# emb_3y_project_2020-11-04_04-35-24.net
KiCad netlist of a schematic drawn in EasyEDA
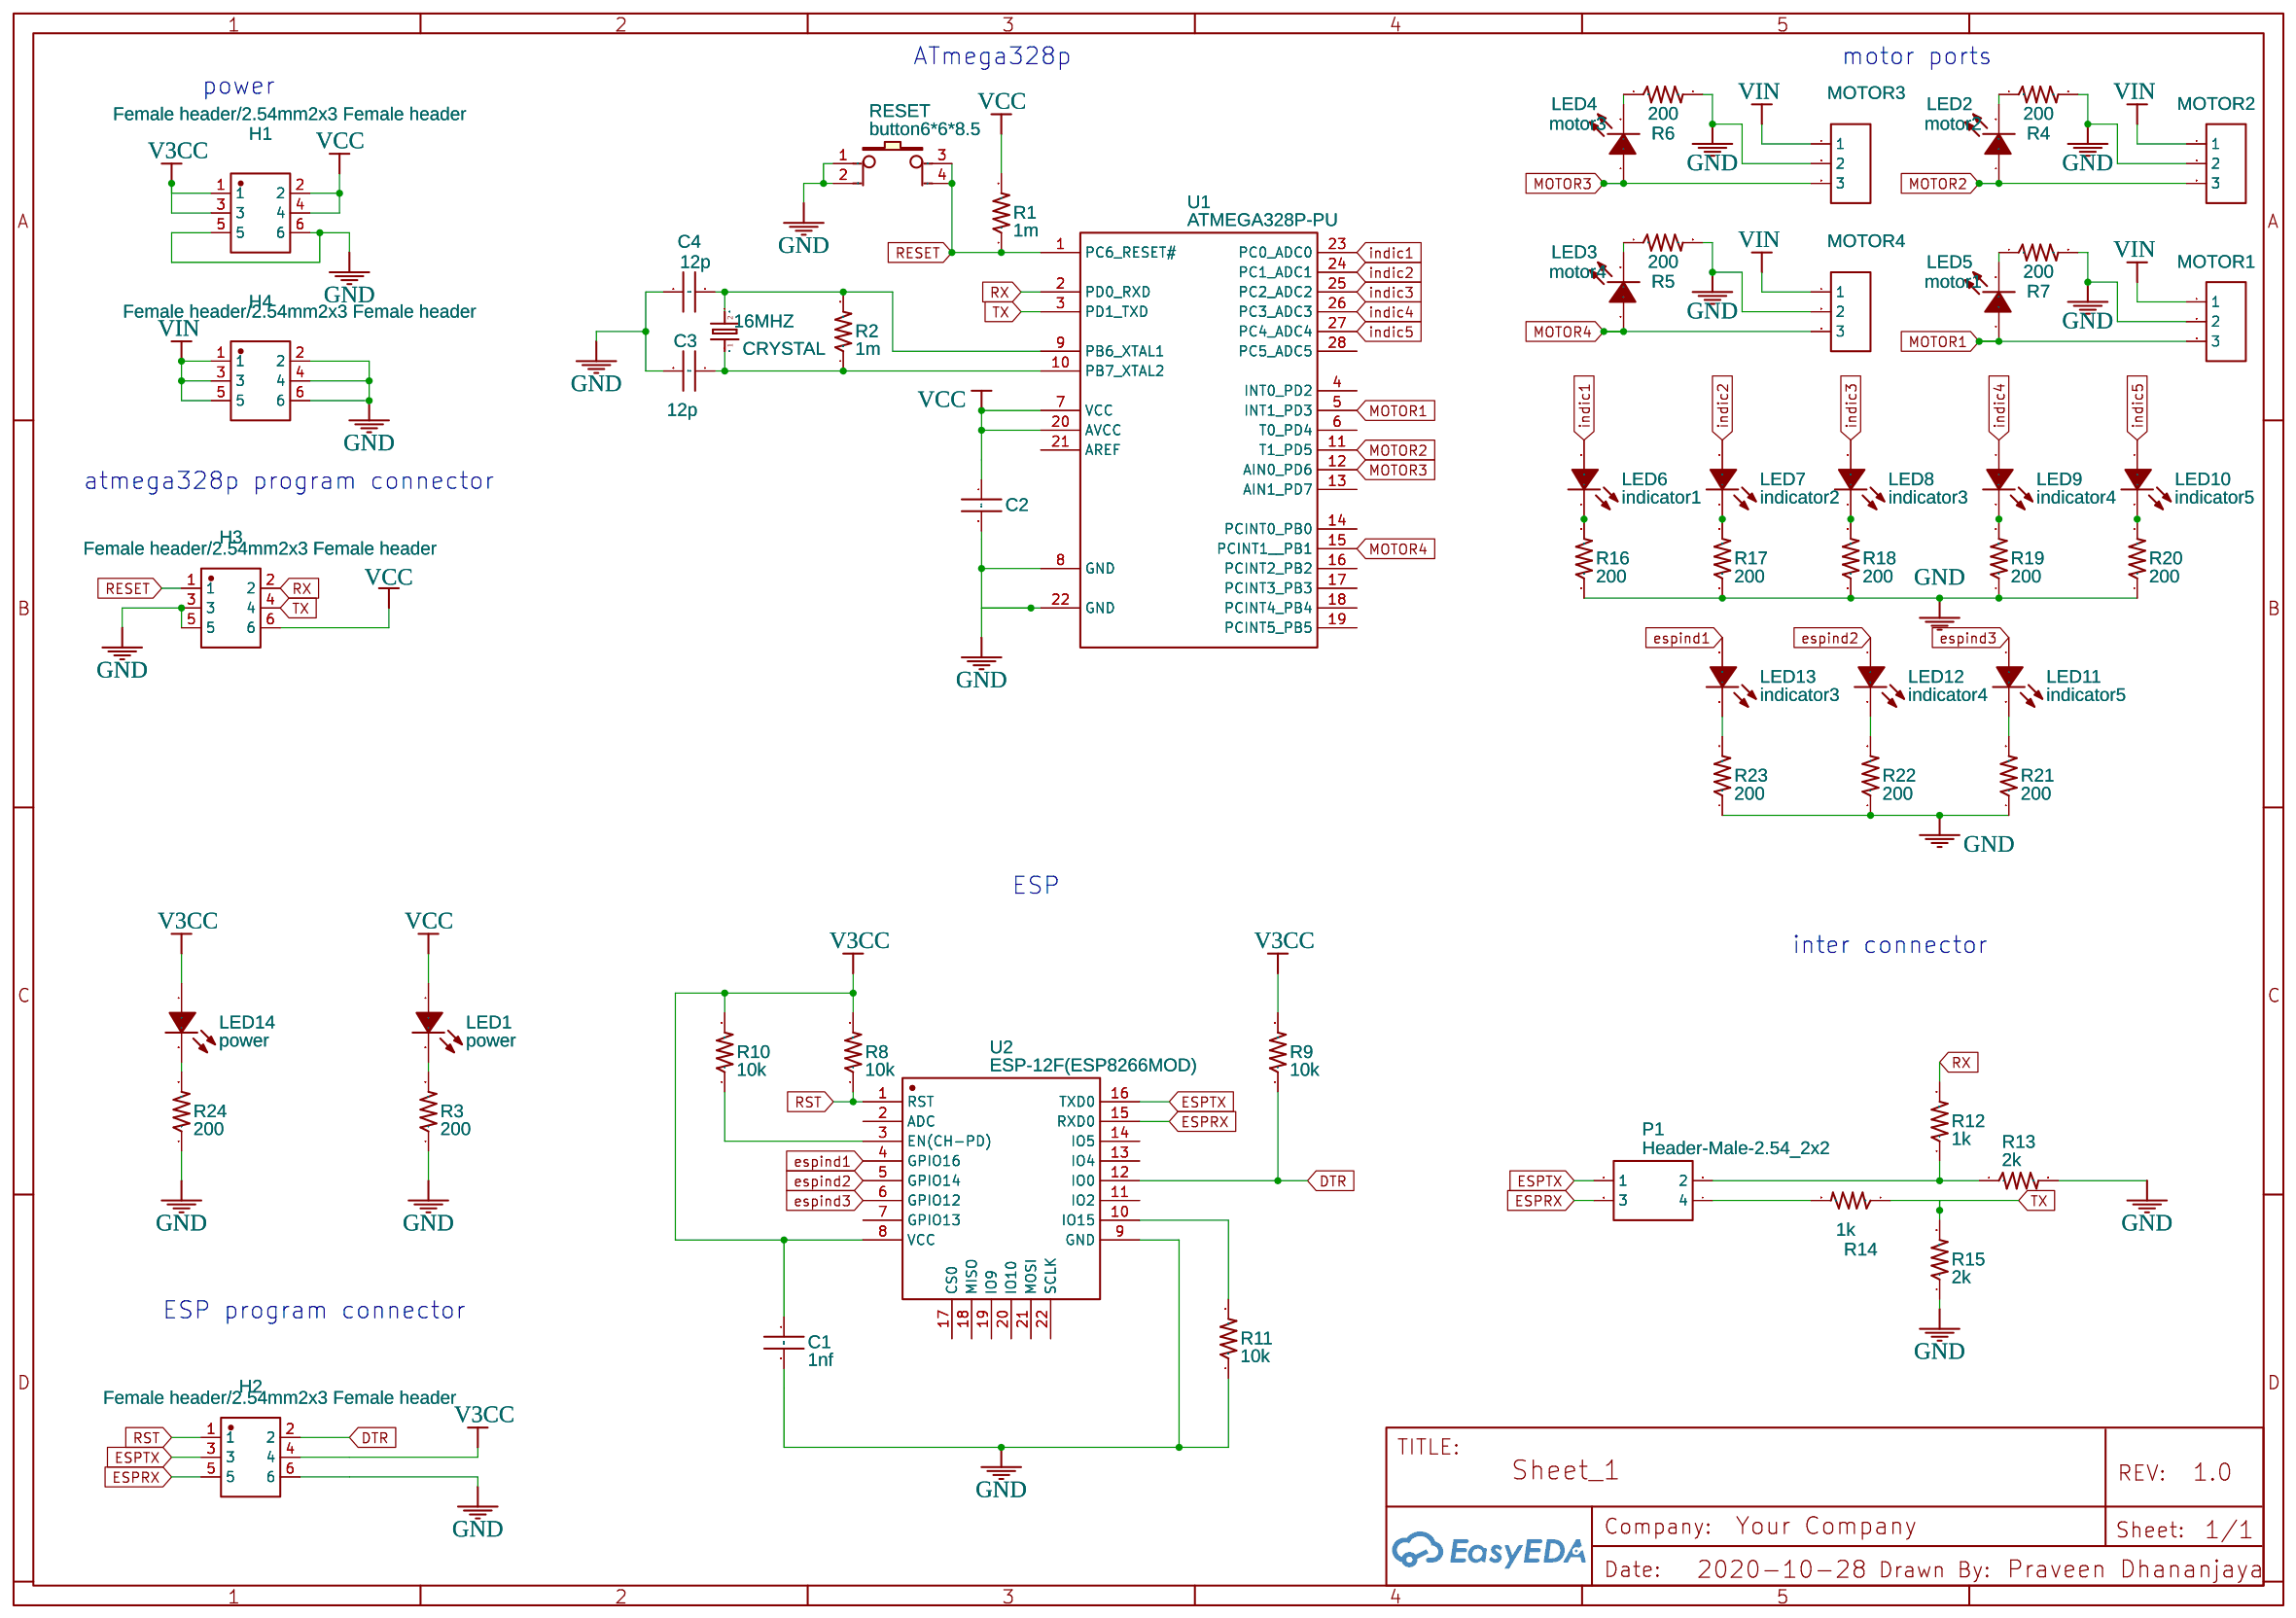
[diagram p0: schematic sheet]

(export (version "E")
  (design (tool "Eeschema 10.0.6"))
  (components
    (comp (ref "16MHZ") (value "CRYSTAL") (libsource (lib "") (part "CRYSTAL")))
    (comp (ref "C1")
      (value "1nf")
      (fields
        (field (name "BOM_Manufacturer Part") "CL21C910JBANNNC")
        (field (name "BOM_Supplier Part") "1276-1836-1-ND")
      )
      (libsource (lib "") (part "CL21C910JBANNNC_2"))
    )
    (comp (ref "C2")
      (value "12p")
      (fields
        (field (name "BOM_Manufacturer Part") "CL21C910JBANNNC")
        (field (name "BOM_Supplier Part") "1276-1836-1-ND")
      )
      (libsource (lib "") (part "CL21C910JBANNNC"))
    )
    (comp (ref "C3")
      (value "12p")
      (fields
        (field (name "BOM_Manufacturer Part") "CL21C910JBANNNC")
        (field (name "BOM_Supplier Part") "1276-1836-1-ND")
      )
      (libsource (lib "") (part "CL21C910JBANNNC_1"))
    )
    (comp (ref "C4")
      (value "12p")
      (fields
        (field (name "BOM_Manufacturer Part") "CL21C910JBANNNC")
        (field (name "BOM_Supplier Part") "1276-1836-1-ND")
      )
      (libsource (lib "") (part "CL21C910JBANNNC_1"))
    )
    (comp (ref "H1")
      (value "Female header/2.54mm2x3 Female header")
      (fields (field (name "BOM_Supplier Part") "C47552"))
      (libsource (lib "") (part "Female header/2.54mm2x3 Female header"))
    )
    (comp (ref "H2")
      (value "Female header/2.54mm2x3 Female header")
      (fields (field (name "BOM_Supplier Part") "C47552"))
      (libsource (lib "") (part "Female header/2.54mm2x3 Female header"))
    )
    (comp (ref "H3")
      (value "Female header/2.54mm2x3 Female header")
      (fields (field (name "BOM_Supplier Part") "C47552"))
      (libsource (lib "") (part "Female header/2.54mm2x3 Female header"))
    )
    (comp (ref "H4")
      (value "Female header/2.54mm2x3 Female header")
      (fields (field (name "BOM_Supplier Part") "C47552"))
      (libsource (lib "") (part "Female header/2.54mm2x3 Female header"))
    )
    (comp (ref "LED1")
      (value "power")
      (fields
        (field (name "BOM_Manufacturer Part") "LEDOrange orange 3AO4UD")
        (field (name "BOM_Supplier Part") "C62095")
      )
      (libsource (lib "") (part "LEDOrange orange 3AO4UD"))
    )
    (comp (ref "LED2")
      (value "motor2")
      (fields
        (field (name "BOM_Manufacturer Part") "LEDOrange orange 3AO4UD")
        (field (name "BOM_Supplier Part") "C62095")
      )
      (libsource (lib "") (part "LEDOrange orange 3AO4UD_1"))
    )
    (comp (ref "LED3")
      (value "motor4")
      (fields
        (field (name "BOM_Manufacturer Part") "LEDOrange orange 3AO4UD")
        (field (name "BOM_Supplier Part") "C62095")
      )
      (libsource (lib "") (part "LEDOrange orange 3AO4UD_1"))
    )
    (comp (ref "LED4")
      (value "motor3")
      (fields
        (field (name "BOM_Manufacturer Part") "LEDOrange orange 3AO4UD")
        (field (name "BOM_Supplier Part") "C62095")
      )
      (libsource (lib "") (part "LEDOrange orange 3AO4UD_1"))
    )
    (comp (ref "LED5")
      (value "motor1")
      (fields
        (field (name "BOM_Manufacturer Part") "LEDOrange orange 3AO4UD")
        (field (name "BOM_Supplier Part") "C62095")
      )
      (libsource (lib "") (part "LEDOrange orange 3AO4UD_1"))
    )
    (comp (ref "LED6")
      (value "indicator1")
      (fields
        (field (name "BOM_Manufacturer Part") "LEDOrange orange 3AO4UD")
        (field (name "BOM_Supplier Part") "C62095")
      )
      (libsource (lib "") (part "LEDOrange orange 3AO4UD"))
    )
    (comp (ref "LED7")
      (value "indicator2")
      (fields
        (field (name "BOM_Manufacturer Part") "LEDOrange orange 3AO4UD")
        (field (name "BOM_Supplier Part") "C62095")
      )
      (libsource (lib "") (part "LEDOrange orange 3AO4UD"))
    )
    (comp (ref "LED8")
      (value "indicator3")
      (fields
        (field (name "BOM_Manufacturer Part") "LEDOrange orange 3AO4UD")
        (field (name "BOM_Supplier Part") "C62095")
      )
      (libsource (lib "") (part "LEDOrange orange 3AO4UD"))
    )
    (comp (ref "LED9")
      (value "indicator4")
      (fields
        (field (name "BOM_Manufacturer Part") "LEDOrange orange 3AO4UD")
        (field (name "BOM_Supplier Part") "C62095")
      )
      (libsource (lib "") (part "LEDOrange orange 3AO4UD"))
    )
    (comp (ref "LED10")
      (value "indicator5")
      (fields
        (field (name "BOM_Manufacturer Part") "LEDOrange orange 3AO4UD")
        (field (name "BOM_Supplier Part") "C62095")
      )
      (libsource (lib "") (part "LEDOrange orange 3AO4UD"))
    )
    (comp (ref "LED11")
      (value "indicator5")
      (fields
        (field (name "BOM_Manufacturer Part") "LEDOrange orange 3AO4UD")
        (field (name "BOM_Supplier Part") "C62095")
      )
      (libsource (lib "") (part "LEDOrange orange 3AO4UD"))
    )
    (comp (ref "LED12")
      (value "indicator4")
      (fields
        (field (name "BOM_Manufacturer Part") "LEDOrange orange 3AO4UD")
        (field (name "BOM_Supplier Part") "C62095")
      )
      (libsource (lib "") (part "LEDOrange orange 3AO4UD"))
    )
    (comp (ref "LED13")
      (value "indicator3")
      (fields
        (field (name "BOM_Manufacturer Part") "LEDOrange orange 3AO4UD")
        (field (name "BOM_Supplier Part") "C62095")
      )
      (libsource (lib "") (part "LEDOrange orange 3AO4UD"))
    )
    (comp (ref "LED14")
      (value "power")
      (fields
        (field (name "BOM_Manufacturer Part") "LEDOrange orange 3AO4UD")
        (field (name "BOM_Supplier Part") "C62095")
      )
      (libsource (lib "") (part "LEDOrange orange 3AO4UD"))
    )
    (comp (ref "MOTOR1")
      (value "Header-Male-2.54_1x3")
      (fields
        (field (name "BOM_Manufacturer Part") "Header2.54mm 1*3P")
        (field (name "BOM_Supplier Part") "C49257")
      )
      (libsource (lib "") (part "Header-Male-2.54_1x3"))
    )
    (comp (ref "MOTOR2")
      (value "Header-Male-2.54_1x3")
      (fields
        (field (name "BOM_Manufacturer Part") "Header2.54mm 1*3P")
        (field (name "BOM_Supplier Part") "C49257")
      )
      (libsource (lib "") (part "Header-Male-2.54_1x3"))
    )
    (comp (ref "MOTOR3")
      (value "Header-Male-2.54_1x3")
      (fields
        (field (name "BOM_Manufacturer Part") "Header2.54mm 1*3P")
        (field (name "BOM_Supplier Part") "C49257")
      )
      (libsource (lib "") (part "Header-Male-2.54_1x3"))
    )
    (comp (ref "MOTOR4")
      (value "Header-Male-2.54_1x3")
      (fields
        (field (name "BOM_Manufacturer Part") "Header2.54mm 1*3P")
        (field (name "BOM_Supplier Part") "C49257")
      )
      (libsource (lib "") (part "Header-Male-2.54_1x3"))
    )
    (comp (ref "P1")
      (value "Header-Male-2.54_2x2")
      (fields
        (field (name "BOM_Manufacturer Part") "Double Rows2.54mm2*2pHeaders  Pins")
        (field (name "BOM_Supplier Part") "C66690")
      )
      (libsource (lib "") (part "Header-Male-2.54_2x2"))
    )
    (comp (ref "R1")
      (value "1m")
      (fields (field (name "BOM_Manufacturer Part") "SAMTECH"))
      (libsource (lib "") (part "R_US805"))
    )
    (comp (ref "R2")
      (value "1m")
      (fields (field (name "BOM_Manufacturer Part") "SAMTECH"))
      (libsource (lib "") (part "R_US805"))
    )
    (comp (ref "R3")
      (value "200")
      (fields (field (name "BOM_Manufacturer Part") "SAMTECH"))
      (libsource (lib "") (part "R_US805"))
    )
    (comp (ref "R4")
      (value "200")
      (fields (field (name "BOM_Manufacturer Part") "SAMTECH"))
      (libsource (lib "") (part "R_US805_2"))
    )
    (comp (ref "R5")
      (value "200")
      (fields (field (name "BOM_Manufacturer Part") "SAMTECH"))
      (libsource (lib "") (part "R_US805_2"))
    )
    (comp (ref "R6")
      (value "200")
      (fields (field (name "BOM_Manufacturer Part") "SAMTECH"))
      (libsource (lib "") (part "R_US805_2"))
    )
    (comp (ref "R7")
      (value "200")
      (fields (field (name "BOM_Manufacturer Part") "SAMTECH"))
      (libsource (lib "") (part "R_US805_2"))
    )
    (comp (ref "R8")
      (value "10k")
      (fields (field (name "BOM_Manufacturer Part") "SAMTECH"))
      (libsource (lib "") (part "R_US805"))
    )
    (comp (ref "R9")
      (value "10k")
      (fields (field (name "BOM_Manufacturer Part") "SAMTECH"))
      (libsource (lib "") (part "R_US805"))
    )
    (comp (ref "R10")
      (value "10k")
      (fields (field (name "BOM_Manufacturer Part") "SAMTECH"))
      (libsource (lib "") (part "R_US805"))
    )
    (comp (ref "R11")
      (value "10k")
      (fields (field (name "BOM_Manufacturer Part") "SAMTECH"))
      (libsource (lib "") (part "R_US805"))
    )
    (comp (ref "R12")
      (value "1k")
      (fields (field (name "BOM_Manufacturer Part") "SAMTECH"))
      (libsource (lib "") (part "R_US805"))
    )
    (comp (ref "R13")
      (value "2k")
      (fields (field (name "BOM_Manufacturer Part") "SAMTECH"))
      (libsource (lib "") (part "R_US805_2"))
    )
    (comp (ref "R14")
      (value "1k")
      (fields (field (name "BOM_Manufacturer Part") "SAMTECH"))
      (libsource (lib "") (part "R_US805_1"))
    )
    (comp (ref "R15")
      (value "2k")
      (fields (field (name "BOM_Manufacturer Part") "SAMTECH"))
      (libsource (lib "") (part "R_US805"))
    )
    (comp (ref "R16")
      (value "200")
      (fields (field (name "BOM_Manufacturer Part") "SAMTECH"))
      (libsource (lib "") (part "R_US805"))
    )
    (comp (ref "R17")
      (value "200")
      (fields (field (name "BOM_Manufacturer Part") "SAMTECH"))
      (libsource (lib "") (part "R_US805"))
    )
    (comp (ref "R18")
      (value "200")
      (fields (field (name "BOM_Manufacturer Part") "SAMTECH"))
      (libsource (lib "") (part "R_US805"))
    )
    (comp (ref "R19")
      (value "200")
      (fields (field (name "BOM_Manufacturer Part") "SAMTECH"))
      (libsource (lib "") (part "R_US805"))
    )
    (comp (ref "R20")
      (value "200")
      (fields (field (name "BOM_Manufacturer Part") "SAMTECH"))
      (libsource (lib "") (part "R_US805"))
    )
    (comp (ref "R21")
      (value "200")
      (fields (field (name "BOM_Manufacturer Part") "SAMTECH"))
      (libsource (lib "") (part "R_US805"))
    )
    (comp (ref "R22")
      (value "200")
      (fields (field (name "BOM_Manufacturer Part") "SAMTECH"))
      (libsource (lib "") (part "R_US805"))
    )
    (comp (ref "R23")
      (value "200")
      (fields (field (name "BOM_Manufacturer Part") "SAMTECH"))
      (libsource (lib "") (part "R_US805"))
    )
    (comp (ref "R24")
      (value "200")
      (fields (field (name "BOM_Manufacturer Part") "SAMTECH"))
      (libsource (lib "") (part "R_US805"))
    )
    (comp (ref "RESET")
      (value "button6*6*8.5")
      (fields (field (name "BOM_Supplier Part") "C59980"))
      (libsource (lib "") (part "button6*6*8.5"))
    )
    (comp (ref "U1")
      (value "ATMEGA328P-PU")
      (fields (field (name "BOM_Supplier Part") "C33901"))
      (libsource (lib "") (part "ATMEGA328P-PU"))
    )
    (comp (ref "U2")
      (value "ESP-12F(ESP8266MOD)")
      (fields (field (name "BOM_Supplier Part") "C82891"))
      (libsource (lib "") (part "ESP-12F(ESP8266MOD)"))
    )
  )
  (nets
    (net (code "1") (name "DTR") (class "Default")
      (node (ref "H2") (pin "2") (pinfunction "2_2") (pintype "unspecified"))
      (node (ref "R9") (pin "1") (pinfunction "1_1") (pintype "unspecified"))
      (node (ref "U2") (pin "12") (pinfunction "IO0_12") (pintype "unspecified"))
    )
    (net (code "2") (name "ESPRX") (class "Default")
      (node (ref "H2") (pin "5") (pinfunction "5_5") (pintype "unspecified"))
      (node (ref "P1") (pin "3") (pinfunction "3_3") (pintype "input"))
      (node (ref "U2") (pin "15") (pinfunction "RXD0_15") (pintype "unspecified"))
    )
    (net (code "3") (name "ESPTX") (class "Default")
      (node (ref "H2") (pin "3") (pinfunction "3_3") (pintype "unspecified"))
      (node (ref "P1") (pin "1") (pinfunction "1_1") (pintype "input"))
      (node (ref "U2") (pin "16") (pinfunction "TXD0_16") (pintype "unspecified"))
    )
    (net (code "4") (name "GND") (class "Default")
      (node (ref "C1") (pin "1") (pinfunction "1_1") (pintype "unspecified"))
      (node (ref "C2") (pin "2") (pinfunction "2_2") (pintype "unspecified"))
      (node (ref "C3") (pin "2") (pinfunction "2_2") (pintype "unspecified"))
      (node (ref "C4") (pin "2") (pinfunction "2_2") (pintype "unspecified"))
      (node (ref "H1") (pin "5") (pinfunction "5_5") (pintype "unspecified"))
      (node (ref "H1") (pin "6") (pinfunction "6_6") (pintype "unspecified"))
      (node (ref "H2") (pin "6") (pinfunction "6_6") (pintype "unspecified"))
      (node (ref "H3") (pin "3") (pinfunction "3_3") (pintype "unspecified"))
      (node (ref "H3") (pin "5") (pinfunction "5_5") (pintype "unspecified"))
      (node (ref "H4") (pin "2") (pinfunction "2_2") (pintype "unspecified"))
      (node (ref "H4") (pin "4") (pinfunction "4_4") (pintype "unspecified"))
      (node (ref "H4") (pin "6") (pinfunction "6_6") (pintype "unspecified"))
      (node (ref "MOTOR1") (pin "2") (pinfunction "2_2") (pintype "input"))
      (node (ref "MOTOR2") (pin "2") (pinfunction "2_2") (pintype "input"))
      (node (ref "MOTOR3") (pin "2") (pinfunction "2_2") (pintype "input"))
      (node (ref "MOTOR4") (pin "2") (pinfunction "2_2") (pintype "input"))
      (node (ref "R11") (pin "1") (pinfunction "1_1") (pintype "unspecified"))
      (node (ref "R13") (pin "2") (pinfunction "2_2") (pintype "unspecified"))
      (node (ref "R15") (pin "1") (pinfunction "1_1") (pintype "unspecified"))
      (node (ref "R16") (pin "1") (pinfunction "1_1") (pintype "unspecified"))
      (node (ref "R17") (pin "1") (pinfunction "1_1") (pintype "unspecified"))
      (node (ref "R18") (pin "1") (pinfunction "1_1") (pintype "unspecified"))
      (node (ref "R19") (pin "1") (pinfunction "1_1") (pintype "unspecified"))
      (node (ref "R20") (pin "1") (pinfunction "1_1") (pintype "unspecified"))
      (node (ref "R21") (pin "1") (pinfunction "1_1") (pintype "unspecified"))
      (node (ref "R22") (pin "1") (pinfunction "1_1") (pintype "unspecified"))
      (node (ref "R23") (pin "1") (pinfunction "1_1") (pintype "unspecified"))
      (node (ref "R24") (pin "1") (pinfunction "1_1") (pintype "unspecified"))
      (node (ref "R3") (pin "1") (pinfunction "1_1") (pintype "unspecified"))
      (node (ref "R4") (pin "2") (pinfunction "2_2") (pintype "unspecified"))
      (node (ref "R5") (pin "2") (pinfunction "2_2") (pintype "unspecified"))
      (node (ref "R6") (pin "2") (pinfunction "2_2") (pintype "unspecified"))
      (node (ref "R7") (pin "2") (pinfunction "2_2") (pintype "unspecified"))
      (node (ref "RESET") (pin "1") (pinfunction "1_1") (pintype "input"))
      (node (ref "RESET") (pin "2") (pinfunction "2_2") (pintype "input"))
      (node (ref "U1") (pin "22") (pinfunction "GND_22") (pintype "passive"))
      (node (ref "U1") (pin "8") (pinfunction "GND_8") (pintype "passive"))
      (node (ref "U2") (pin "9") (pinfunction "GND_9") (pintype "unspecified"))
    )
    (net (code "5") (name "MOTOR1") (class "Default")
      (node (ref "LED5") (pin "1") (pinfunction "A_1") (pintype "unspecified"))
      (node (ref "MOTOR1") (pin "3") (pinfunction "3_3") (pintype "input"))
      (node (ref "U1") (pin "5") (pinfunction "INT1_PD3_5") (pintype "bidirectional"))
    )
    (net (code "6") (name "MOTOR2") (class "Default")
      (node (ref "LED2") (pin "1") (pinfunction "A_1") (pintype "unspecified"))
      (node (ref "MOTOR2") (pin "3") (pinfunction "3_3") (pintype "input"))
      (node (ref "U1") (pin "11") (pinfunction "T1_PD5_11") (pintype "bidirectional"))
    )
    (net (code "7") (name "MOTOR3") (class "Default")
      (node (ref "LED4") (pin "1") (pinfunction "A_1") (pintype "unspecified"))
      (node (ref "MOTOR3") (pin "3") (pinfunction "3_3") (pintype "input"))
      (node (ref "U1") (pin "12") (pinfunction "AIN0_PD6_12") (pintype "bidirectional"))
    )
    (net (code "8") (name "MOTOR4") (class "Default")
      (node (ref "LED3") (pin "1") (pinfunction "A_1") (pintype "unspecified"))
      (node (ref "MOTOR4") (pin "3") (pinfunction "3_3") (pintype "input"))
      (node (ref "U1") (pin "15") (pinfunction "PCINT1__PB1_15") (pintype "bidirectional"))
    )
    (net (code "9") (name "Net-(LED1-K)") (class "Default")
      (node (ref "LED1") (pin "2") (pinfunction "K_2") (pintype "unspecified"))
      (node (ref "R3") (pin "2") (pinfunction "2_2") (pintype "unspecified"))
    )
    (net (code "10") (name "Net-(LED2-K)") (class "Default")
      (node (ref "LED2") (pin "2") (pinfunction "K_2") (pintype "unspecified"))
      (node (ref "R4") (pin "1") (pinfunction "1_1") (pintype "unspecified"))
    )
    (net (code "11") (name "Net-(LED3-K)") (class "Default")
      (node (ref "LED3") (pin "2") (pinfunction "K_2") (pintype "unspecified"))
      (node (ref "R5") (pin "1") (pinfunction "1_1") (pintype "unspecified"))
    )
    (net (code "12") (name "Net-(LED4-K)") (class "Default")
      (node (ref "LED4") (pin "2") (pinfunction "K_2") (pintype "unspecified"))
      (node (ref "R6") (pin "1") (pinfunction "1_1") (pintype "unspecified"))
    )
    (net (code "13") (name "Net-(LED5-K)") (class "Default")
      (node (ref "LED5") (pin "2") (pinfunction "K_2") (pintype "unspecified"))
      (node (ref "R7") (pin "1") (pinfunction "1_1") (pintype "unspecified"))
    )
    (net (code "14") (name "Net-(LED6-K)") (class "Default")
      (node (ref "LED6") (pin "2") (pinfunction "K_2") (pintype "unspecified"))
      (node (ref "R16") (pin "2") (pinfunction "2_2") (pintype "unspecified"))
    )
    (net (code "15") (name "Net-(LED7-K)") (class "Default")
      (node (ref "LED7") (pin "2") (pinfunction "K_2") (pintype "unspecified"))
      (node (ref "R17") (pin "2") (pinfunction "2_2") (pintype "unspecified"))
    )
    (net (code "16") (name "Net-(LED8-K)") (class "Default")
      (node (ref "LED8") (pin "2") (pinfunction "K_2") (pintype "unspecified"))
      (node (ref "R18") (pin "2") (pinfunction "2_2") (pintype "unspecified"))
    )
    (net (code "17") (name "Net-(LED9-K)") (class "Default")
      (node (ref "LED9") (pin "2") (pinfunction "K_2") (pintype "unspecified"))
      (node (ref "R19") (pin "2") (pinfunction "2_2") (pintype "unspecified"))
    )
    (net (code "18") (name "Net-(LED10-K)") (class "Default")
      (node (ref "LED10") (pin "2") (pinfunction "K_2") (pintype "unspecified"))
      (node (ref "R20") (pin "2") (pinfunction "2_2") (pintype "unspecified"))
    )
    (net (code "19") (name "Net-(LED11-K)") (class "Default")
      (node (ref "LED11") (pin "2") (pinfunction "K_2") (pintype "unspecified"))
      (node (ref "R21") (pin "2") (pinfunction "2_2") (pintype "unspecified"))
    )
    (net (code "20") (name "Net-(LED12-K)") (class "Default")
      (node (ref "LED12") (pin "2") (pinfunction "K_2") (pintype "unspecified"))
      (node (ref "R22") (pin "2") (pinfunction "2_2") (pintype "unspecified"))
    )
    (net (code "21") (name "Net-(LED13-K)") (class "Default")
      (node (ref "LED13") (pin "2") (pinfunction "K_2") (pintype "unspecified"))
      (node (ref "R23") (pin "2") (pinfunction "2_2") (pintype "unspecified"))
    )
    (net (code "22") (name "Net-(LED14-K)") (class "Default")
      (node (ref "LED14") (pin "2") (pinfunction "K_2") (pintype "unspecified"))
      (node (ref "R24") (pin "2") (pinfunction "2_2") (pintype "unspecified"))
    )
    (net (code "23") (name "Net-(P1-Pad2)") (class "Default")
      (node (ref "P1") (pin "2") (pinfunction "2_2") (pintype "input"))
      (node (ref "R12") (pin "1") (pinfunction "1_1") (pintype "unspecified"))
      (node (ref "R13") (pin "1") (pinfunction "1_1") (pintype "unspecified"))
    )
    (net (code "24") (name "Net-(P1-Pad4)") (class "Default")
      (node (ref "P1") (pin "4") (pinfunction "4_4") (pintype "input"))
      (node (ref "R14") (pin "2") (pinfunction "2_2") (pintype "unspecified"))
    )
    (net (code "25") (name "Net-(U1-PB6_XTAL1)") (class "Default")
      (node (ref "16MHZ") (pin "2") (pinfunction "2_2") (pintype "unspecified"))
      (node (ref "C4") (pin "1") (pinfunction "1_1") (pintype "unspecified"))
      (node (ref "R2") (pin "2") (pinfunction "2_2") (pintype "unspecified"))
      (node (ref "U1") (pin "9") (pinfunction "PB6_XTAL1_9") (pintype "bidirectional"))
    )
    (net (code "26") (name "Net-(U1-PB7_XTAL2)") (class "Default")
      (node (ref "16MHZ") (pin "1") (pinfunction "1_1") (pintype "unspecified"))
      (node (ref "C3") (pin "1") (pinfunction "1_1") (pintype "unspecified"))
      (node (ref "R2") (pin "1") (pinfunction "1_1") (pintype "unspecified"))
      (node (ref "U1") (pin "10") (pinfunction "PB7_XTAL2_10") (pintype "bidirectional"))
    )
    (net (code "27") (name "Net-(U2-EN(CH-PD))") (class "Default")
      (node (ref "R10") (pin "1") (pinfunction "1_1") (pintype "unspecified"))
      (node (ref "U2") (pin "3") (pinfunction "EN(CH-PD)_3") (pintype "unspecified"))
    )
    (net (code "28") (name "Net-(U2-IO15)") (class "Default")
      (node (ref "R11") (pin "2") (pinfunction "2_2") (pintype "unspecified"))
      (node (ref "U2") (pin "10") (pinfunction "IO15_10") (pintype "unspecified"))
    )
    (net (code "29") (name "RESET") (class "Default")
      (node (ref "H3") (pin "1") (pinfunction "1_1") (pintype "unspecified"))
      (node (ref "R1") (pin "1") (pinfunction "1_1") (pintype "unspecified"))
      (node (ref "RESET") (pin "3") (pinfunction "3_3") (pintype "input"))
      (node (ref "RESET") (pin "4") (pinfunction "4_4") (pintype "input"))
      (node (ref "U1") (pin "1") (pinfunction "PC6_RESET#_1") (pintype "bidirectional"))
    )
    (net (code "30") (name "RST") (class "Default")
      (node (ref "H2") (pin "1") (pinfunction "1_1") (pintype "unspecified"))
      (node (ref "R8") (pin "1") (pinfunction "1_1") (pintype "unspecified"))
      (node (ref "U2") (pin "1") (pinfunction "RST_1") (pintype "unspecified"))
    )
    (net (code "31") (name "RX") (class "Default")
      (node (ref "H3") (pin "2") (pinfunction "2_2") (pintype "unspecified"))
      (node (ref "R12") (pin "2") (pinfunction "2_2") (pintype "unspecified"))
      (node (ref "U1") (pin "2") (pinfunction "PD0_RXD_2") (pintype "bidirectional"))
    )
    (net (code "32") (name "TX") (class "Default")
      (node (ref "H3") (pin "4") (pinfunction "4_4") (pintype "unspecified"))
      (node (ref "R14") (pin "1") (pinfunction "1_1") (pintype "unspecified"))
      (node (ref "R15") (pin "2") (pinfunction "2_2") (pintype "unspecified"))
      (node (ref "U1") (pin "3") (pinfunction "PD1_TXD_3") (pintype "bidirectional"))
    )
    (net (code "33") (name "V3CC") (class "Default")
      (node (ref "C1") (pin "2") (pinfunction "2_2") (pintype "unspecified"))
      (node (ref "H1") (pin "1") (pinfunction "1_1") (pintype "unspecified"))
      (node (ref "H1") (pin "3") (pinfunction "3_3") (pintype "unspecified"))
      (node (ref "H2") (pin "4") (pinfunction "4_4") (pintype "unspecified"))
      (node (ref "LED14") (pin "1") (pinfunction "A_1") (pintype "unspecified"))
      (node (ref "R10") (pin "2") (pinfunction "2_2") (pintype "unspecified"))
      (node (ref "R8") (pin "2") (pinfunction "2_2") (pintype "unspecified"))
      (node (ref "R9") (pin "2") (pinfunction "2_2") (pintype "unspecified"))
      (node (ref "U2") (pin "8") (pinfunction "VCC_8") (pintype "unspecified"))
    )
    (net (code "34") (name "VCC") (class "Default")
      (node (ref "C2") (pin "1") (pinfunction "1_1") (pintype "unspecified"))
      (node (ref "H1") (pin "2") (pinfunction "2_2") (pintype "unspecified"))
      (node (ref "H1") (pin "4") (pinfunction "4_4") (pintype "unspecified"))
      (node (ref "H3") (pin "6") (pinfunction "6_6") (pintype "unspecified"))
      (node (ref "LED1") (pin "1") (pinfunction "A_1") (pintype "unspecified"))
      (node (ref "R1") (pin "2") (pinfunction "2_2") (pintype "unspecified"))
      (node (ref "U1") (pin "20") (pinfunction "AVCC_20") (pintype "passive"))
      (node (ref "U1") (pin "7") (pinfunction "VCC_7") (pintype "passive"))
    )
    (net (code "35") (name "VIN") (class "Default")
      (node (ref "H4") (pin "1") (pinfunction "1_1") (pintype "unspecified"))
      (node (ref "H4") (pin "3") (pinfunction "3_3") (pintype "unspecified"))
      (node (ref "H4") (pin "5") (pinfunction "5_5") (pintype "unspecified"))
      (node (ref "MOTOR1") (pin "1") (pinfunction "1_1") (pintype "input"))
      (node (ref "MOTOR2") (pin "1") (pinfunction "1_1") (pintype "input"))
      (node (ref "MOTOR3") (pin "1") (pinfunction "1_1") (pintype "input"))
      (node (ref "MOTOR4") (pin "1") (pinfunction "1_1") (pintype "input"))
    )
    (net (code "36") (name "espind1") (class "Default")
      (node (ref "LED13") (pin "1") (pinfunction "A_1") (pintype "unspecified"))
      (node (ref "U2") (pin "4") (pinfunction "GPIO16_4") (pintype "unspecified"))
    )
    (net (code "37") (name "espind2") (class "Default")
      (node (ref "LED12") (pin "1") (pinfunction "A_1") (pintype "unspecified"))
      (node (ref "U2") (pin "5") (pinfunction "GPIO14_5") (pintype "unspecified"))
    )
    (net (code "38") (name "espind3") (class "Default")
      (node (ref "LED11") (pin "1") (pinfunction "A_1") (pintype "unspecified"))
      (node (ref "U2") (pin "6") (pinfunction "GPIO12_6") (pintype "unspecified"))
    )
    (net (code "39") (name "indic1") (class "Default")
      (node (ref "LED6") (pin "1") (pinfunction "A_1") (pintype "unspecified"))
      (node (ref "U1") (pin "23") (pinfunction "PC0_ADC0_23") (pintype "bidirectional"))
    )
    (net (code "40") (name "indic2") (class "Default")
      (node (ref "LED7") (pin "1") (pinfunction "A_1") (pintype "unspecified"))
      (node (ref "U1") (pin "24") (pinfunction "PC1_ADC1_24") (pintype "bidirectional"))
    )
    (net (code "41") (name "indic3") (class "Default")
      (node (ref "LED8") (pin "1") (pinfunction "A_1") (pintype "unspecified"))
      (node (ref "U1") (pin "25") (pinfunction "PC2_ADC2_25") (pintype "bidirectional"))
    )
    (net (code "42") (name "indic4") (class "Default")
      (node (ref "LED9") (pin "1") (pinfunction "A_1") (pintype "unspecified"))
      (node (ref "U1") (pin "26") (pinfunction "PC3_ADC3_26") (pintype "bidirectional"))
    )
    (net (code "43") (name "indic5") (class "Default")
      (node (ref "LED10") (pin "1") (pinfunction "A_1") (pintype "unspecified"))
      (node (ref "U1") (pin "27") (pinfunction "PC4_ADC4_27") (pintype "bidirectional"))
    )
    (net (code "44") (name "unconnected-(U1-AIN1_PD7-Pad13)") (class "Default")
      (node (ref "U1") (pin "13") (pinfunction "AIN1_PD7_13") (pintype "bidirectional"))
    )
    (net (code "45") (name "unconnected-(U1-AREF-Pad21)") (class "Default")
      (node (ref "U1") (pin "21") (pinfunction "AREF_21") (pintype "passive"))
    )
    (net (code "46") (name "unconnected-(U1-INT0_PD2-Pad4)") (class "Default")
      (node (ref "U1") (pin "4") (pinfunction "INT0_PD2_4") (pintype "bidirectional"))
    )
    (net (code "47") (name "unconnected-(U1-PC5_ADC5-Pad28)") (class "Default")
      (node (ref "U1") (pin "28") (pinfunction "PC5_ADC5_28") (pintype "bidirectional"))
    )
    (net (code "48") (name "unconnected-(U1-PCINT0_PB0-Pad14)") (class "Default")
      (node (ref "U1") (pin "14") (pinfunction "PCINT0_PB0_14") (pintype "bidirectional"))
    )
    (net (code "49") (name "unconnected-(U1-PCINT2_PB2-Pad16)") (class "Default")
      (node (ref "U1") (pin "16") (pinfunction "PCINT2_PB2_16") (pintype "bidirectional"))
    )
    (net (code "50") (name "unconnected-(U1-PCINT3_PB3-Pad17)") (class "Default")
      (node (ref "U1") (pin "17") (pinfunction "PCINT3_PB3_17") (pintype "bidirectional"))
    )
    (net (code "51") (name "unconnected-(U1-PCINT4_PB4-Pad18)") (class "Default")
      (node (ref "U1") (pin "18") (pinfunction "PCINT4_PB4_18") (pintype "bidirectional"))
    )
    (net (code "52") (name "unconnected-(U1-PCINT5_PB5-Pad19)") (class "Default")
      (node (ref "U1") (pin "19") (pinfunction "PCINT5_PB5_19") (pintype "bidirectional"))
    )
    (net (code "53") (name "unconnected-(U1-T0_PD4-Pad6)") (class "Default")
      (node (ref "U1") (pin "6") (pinfunction "T0_PD4_6") (pintype "bidirectional"))
    )
    (net (code "54") (name "unconnected-(U2-ADC-Pad2)") (class "Default")
      (node (ref "U2") (pin "2") (pinfunction "ADC_2") (pintype "unspecified"))
    )
    (net (code "55") (name "unconnected-(U2-CS0-Pad17)") (class "Default")
      (node (ref "U2") (pin "17") (pinfunction "CS0_17") (pintype "unspecified"))
    )
    (net (code "56") (name "unconnected-(U2-GPIO13-Pad7)") (class "Default")
      (node (ref "U2") (pin "7") (pinfunction "GPIO13_7") (pintype "unspecified"))
    )
    (net (code "57") (name "unconnected-(U2-IO2-Pad11)") (class "Default")
      (node (ref "U2") (pin "11") (pinfunction "IO2_11") (pintype "unspecified"))
    )
    (net (code "58") (name "unconnected-(U2-IO4-Pad13)") (class "Default")
      (node (ref "U2") (pin "13") (pinfunction "IO4_13") (pintype "unspecified"))
    )
    (net (code "59") (name "unconnected-(U2-IO5-Pad14)") (class "Default")
      (node (ref "U2") (pin "14") (pinfunction "IO5_14") (pintype "unspecified"))
    )
    (net (code "60") (name "unconnected-(U2-IO9-Pad19)") (class "Default")
      (node (ref "U2") (pin "19") (pinfunction "IO9_19") (pintype "unspecified"))
    )
    (net (code "61") (name "unconnected-(U2-IO10-Pad20)") (class "Default")
      (node (ref "U2") (pin "20") (pinfunction "IO10_20") (pintype "unspecified"))
    )
    (net (code "62") (name "unconnected-(U2-MISO-Pad18)") (class "Default")
      (node (ref "U2") (pin "18") (pinfunction "MISO_18") (pintype "unspecified"))
    )
    (net (code "63") (name "unconnected-(U2-MOSI-Pad21)") (class "Default")
      (node (ref "U2") (pin "21") (pinfunction "MOSI_21") (pintype "unspecified"))
    )
    (net (code "64") (name "unconnected-(U2-SCLK-Pad22)") (class "Default")
      (node (ref "U2") (pin "22") (pinfunction "SCLK_22") (pintype "unspecified"))
    )
  )
)
